# czujniki.net
KiCad netlist of a schematic drawn in EAGLE
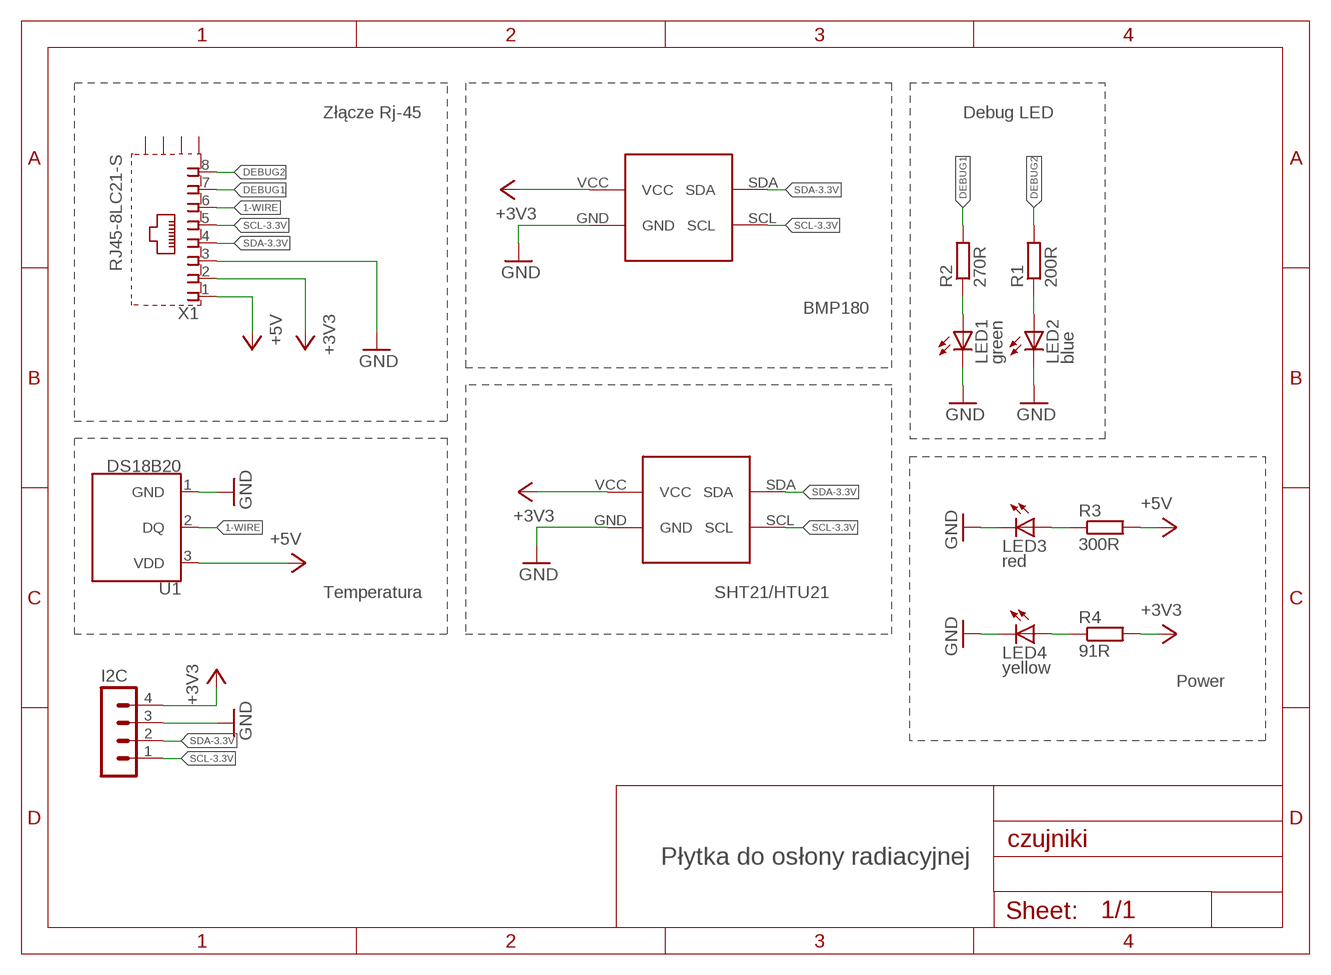
[diagram p0: schematic, sheet 1]

(export (version "E")
  (design (tool "Eeschema 10.0.6"))
  (components
    (comp (ref "I2C")
      (value "MA04-1")
      (footprint "eagle-import:MA04-1")
      (libsource (lib "eagle-import") (part "MA04-1"))
    )
    (comp (ref "LED1")
      (value "green")
      (footprint "eagle-import:CHIPLED_1206")
      (libsource (lib "eagle-import") (part "LEDCHIPLED_1206"))
    )
    (comp (ref "LED2")
      (value "blue")
      (footprint "eagle-import:CHIPLED_1206")
      (libsource (lib "eagle-import") (part "LEDCHIPLED_1206"))
    )
    (comp (ref "LED3")
      (value "red")
      (footprint "eagle-import:CHIPLED_1206")
      (libsource (lib "eagle-import") (part "LEDCHIPLED_1206"))
    )
    (comp (ref "LED4")
      (value "yellow")
      (footprint "eagle-import:CHIPLED_1206")
      (libsource (lib "eagle-import") (part "LEDCHIPLED_1206"))
    )
    (comp (ref "R1")
      (value "200R")
      (footprint "eagle-import:M0805")
      (libsource (lib "eagle-import") (part "R-EU_M0805"))
    )
    (comp (ref "R2")
      (value "270R")
      (footprint "eagle-import:M0805")
      (libsource (lib "eagle-import") (part "R-EU_M0805"))
    )
    (comp (ref "R3")
      (value "300R")
      (footprint "eagle-import:M0805")
      (libsource (lib "eagle-import") (part "R-EU_M0805"))
    )
    (comp (ref "R4")
      (value "91R")
      (footprint "eagle-import:M0805")
      (libsource (lib "eagle-import") (part "R-EU_M0805"))
    )
    (comp (ref "U$1")
      (value "BMP180")
      (footprint "eagle-import:BMP180")
      (libsource (lib "eagle-import") (part "BMP180"))
    )
    (comp (ref "U$2")
      (value "I2C_BOARD")
      (footprint "eagle-import:I2C_BOARD")
      (libsource (lib "eagle-import") (part "I2C_BOARD"))
    )
    (comp (ref "U1")
      (value "DS18B20")
      (footprint "eagle-import:TO-92-AMMO")
      (libsource (lib "eagle-import") (part "DS18B20"))
    )
    (comp (ref "X1")
      (value "RJ45-8LC21-S")
      (footprint "eagle-import:RJ45-SHIELD1")
      (libsource (lib "eagle-import") (part "RJ4521-S-8LC"))
    )
  )
  (nets
    (net (code "1") (name "+3V3") (class "Default")
      (node (ref "I2C") (pin "4") (pinfunction "4_4") (pintype "passive"))
      (node (ref "R4") (pin "2") (pinfunction "2_2") (pintype "passive"))
      (node (ref "U$1") (pin "VCC") (pinfunction "VCC_VCC") (pintype "bidirectional"))
      (node (ref "U$2") (pin "VCC") (pinfunction "VCC_VCC") (pintype "bidirectional"))
      (node (ref "X1") (pin "2") (pinfunction "2_2") (pintype "passive"))
    )
    (net (code "2") (name "+5V") (class "Default")
      (node (ref "R3") (pin "2") (pinfunction "2_2") (pintype "passive"))
      (node (ref "U1") (pin "3") (pinfunction "VDD_3") (pintype "power_in"))
      (node (ref "X1") (pin "1") (pinfunction "1_1") (pintype "passive"))
    )
    (net (code "3") (name "1-WIRE") (class "Default")
      (node (ref "U1") (pin "2") (pinfunction "DQ_2") (pintype "bidirectional"))
      (node (ref "X1") (pin "6") (pinfunction "6_6") (pintype "passive"))
    )
    (net (code "4") (name "DEBUG1") (class "Default")
      (node (ref "R2") (pin "2") (pinfunction "2_2") (pintype "passive"))
      (node (ref "X1") (pin "7") (pinfunction "7_7") (pintype "passive"))
    )
    (net (code "5") (name "DEBUG2") (class "Default")
      (node (ref "R1") (pin "2") (pinfunction "2_2") (pintype "passive"))
      (node (ref "X1") (pin "8") (pinfunction "8_8") (pintype "passive"))
    )
    (net (code "6") (name "GND") (class "Default")
      (node (ref "I2C") (pin "3") (pinfunction "3_3") (pintype "passive"))
      (node (ref "LED1") (pin "C") (pinfunction "C_C") (pintype "passive"))
      (node (ref "LED2") (pin "C") (pinfunction "C_C") (pintype "passive"))
      (node (ref "LED3") (pin "C") (pinfunction "C_C") (pintype "passive"))
      (node (ref "LED4") (pin "C") (pinfunction "C_C") (pintype "passive"))
      (node (ref "U$1") (pin "GND") (pinfunction "GND_GND") (pintype "bidirectional"))
      (node (ref "U$2") (pin "GND") (pinfunction "GND_GND") (pintype "bidirectional"))
      (node (ref "U1") (pin "1") (pinfunction "GND_1") (pintype "power_in"))
      (node (ref "X1") (pin "3") (pinfunction "3_3") (pintype "passive"))
    )
    (net (code "7") (name "Net-(LED1-PadA)") (class "Default")
      (node (ref "LED1") (pin "A") (pinfunction "A_A") (pintype "passive"))
      (node (ref "R2") (pin "1") (pinfunction "1_1") (pintype "passive"))
    )
    (net (code "8") (name "Net-(LED2-PadA)") (class "Default")
      (node (ref "LED2") (pin "A") (pinfunction "A_A") (pintype "passive"))
      (node (ref "R1") (pin "1") (pinfunction "1_1") (pintype "passive"))
    )
    (net (code "9") (name "Net-(LED3-PadA)") (class "Default")
      (node (ref "LED3") (pin "A") (pinfunction "A_A") (pintype "passive"))
      (node (ref "R3") (pin "1") (pinfunction "1_1") (pintype "passive"))
    )
    (net (code "10") (name "Net-(LED4-PadA)") (class "Default")
      (node (ref "LED4") (pin "A") (pinfunction "A_A") (pintype "passive"))
      (node (ref "R4") (pin "1") (pinfunction "1_1") (pintype "passive"))
    )
    (net (code "11") (name "SCL-3.3V") (class "Default")
      (node (ref "I2C") (pin "1") (pinfunction "1_1") (pintype "passive"))
      (node (ref "U$1") (pin "SCL") (pinfunction "SCL_SCL") (pintype "bidirectional"))
      (node (ref "U$2") (pin "SCL") (pinfunction "SCL_SCL") (pintype "bidirectional"))
      (node (ref "X1") (pin "5") (pinfunction "5_5") (pintype "passive"))
    )
    (net (code "12") (name "SDA-3.3V") (class "Default")
      (node (ref "I2C") (pin "2") (pinfunction "2_2") (pintype "passive"))
      (node (ref "U$1") (pin "SDA") (pinfunction "SDA_SDA") (pintype "bidirectional"))
      (node (ref "U$2") (pin "SDA") (pinfunction "SDA_SDA") (pintype "bidirectional"))
      (node (ref "X1") (pin "4") (pinfunction "4_4") (pintype "passive"))
    )
    (net (code "13") (name "unconnected-(X1-S-PadS1)") (class "Default")
      (node (ref "X1") (pin "S1") (pinfunction "S_S1") (pintype "passive"))
    )
    (net (code "14") (name "unconnected-(X1-S-PadS2)") (class "Default")
      (node (ref "X1") (pin "S2") (pinfunction "S_S2") (pintype "passive"))
    )
    (net (code "15") (name "unconnected-(X1-S-PadS3)") (class "Default")
      (node (ref "X1") (pin "S3") (pinfunction "S_S3") (pintype "passive"))
    )
    (net (code "16") (name "unconnected-(X1-S-PadS4)") (class "Default")
      (node (ref "X1") (pin "S4") (pinfunction "S_S4") (pintype "passive"))
    )
  )
)
